# LabPowerSupply_CurrentModuleV1_0.net
KiCad netlist of a schematic drawn in EAGLE
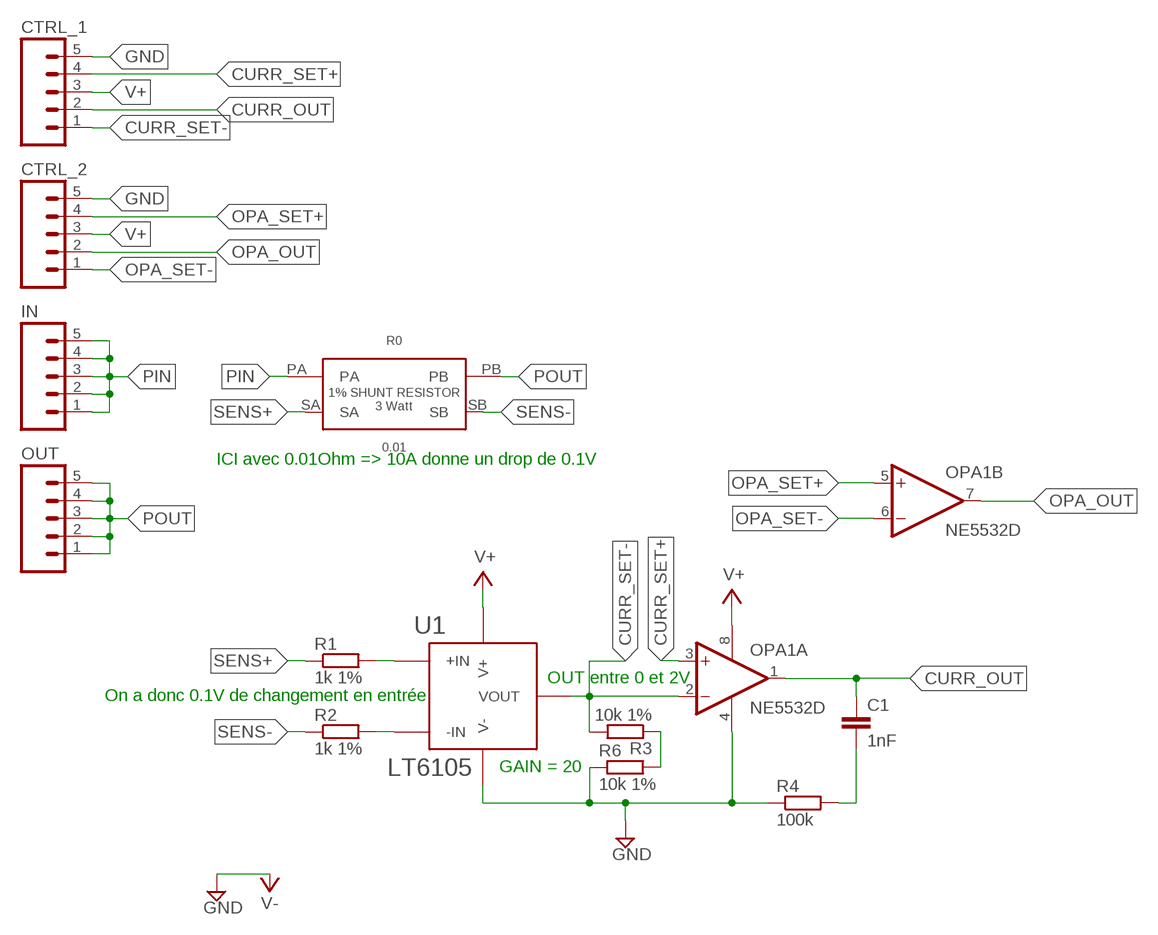
[diagram p0: schematic, sheet 1]

(export (version "E")
  (design (tool "Eeschema 10.0.6"))
  (components
    (comp (ref "C1")
      (value "1nF")
      (footprint "eagle-import:C1206K")
      (libsource (lib "eagle-import") (part "C-EUC1206K"))
    )
    (comp (ref "CTRL_1")
      (value "M05PTH_LONGPADS")
      (footprint "eagle-import:1X05_LONGPADS")
      (libsource (lib "eagle-import") (part "M05PTH_LONGPADS"))
    )
    (comp (ref "CTRL_2")
      (value "M05PTH_LONGPADS")
      (footprint "eagle-import:1X05_LONGPADS")
      (libsource (lib "eagle-import") (part "M05PTH_LONGPADS"))
    )
    (comp (ref "IN")
      (value "M05PTH_LONGPADS")
      (footprint "eagle-import:1X05_LONGPADS")
      (libsource (lib "eagle-import") (part "M05PTH_LONGPADS"))
    )
    (comp (ref "OPA1")
      (value "NE5532D")
      (footprint "eagle-import:SO08")
      (libsource (lib "eagle-import") (part "NE5532D"))
    )
    (comp (ref "OUT")
      (value "M05PTH_LONGPADS")
      (footprint "eagle-import:1X05_LONGPADS")
      (libsource (lib "eagle-import") (part "M05PTH_LONGPADS"))
    )
    (comp (ref "R0")
      (value "0.01")
      (footprint "eagle-import:3637R")
      (libsource (lib "eagle-import") (part "WSL3637R0100FEA"))
    )
    (comp (ref "R1")
      (value "1k 1%")
      (footprint "eagle-import:R1206")
      (libsource (lib "eagle-import") (part "R-EU_R1206"))
    )
    (comp (ref "R2")
      (value "1k 1%")
      (footprint "eagle-import:R1206")
      (libsource (lib "eagle-import") (part "R-EU_R1206"))
    )
    (comp (ref "R3")
      (value "10k 1%")
      (footprint "eagle-import:R1206")
      (libsource (lib "eagle-import") (part "R-EU_R1206"))
    )
    (comp (ref "R4")
      (value "100k")
      (footprint "eagle-import:R1206")
      (libsource (lib "eagle-import") (part "R-EU_R1206"))
    )
    (comp (ref "R6")
      (value "10k 1%")
      (footprint "eagle-import:R1206")
      (libsource (lib "eagle-import") (part "R-EU_R1206"))
    )
    (comp (ref "U1")
      (value "LT6105")
      (footprint "eagle-import:MSOP_8")
      (libsource (lib "eagle-import") (part "LT6105_MSOP_8"))
    )
  )
  (nets
    (net (code "1") (name "CURR_OUT") (class "Default")
      (node (ref "C1") (pin "1") (pinfunction "1_1") (pintype "passive"))
      (node (ref "CTRL_1") (pin "2") (pinfunction "2_2") (pintype "passive"))
      (node (ref "OPA1") (pin "1") (pinfunction "OUT_1") (pintype "output"))
    )
    (net (code "2") (name "CURR_SET+") (class "Default")
      (node (ref "CTRL_1") (pin "4") (pinfunction "4_4") (pintype "passive"))
      (node (ref "OPA1") (pin "3") (pinfunction "+IN_3") (pintype "input"))
    )
    (net (code "3") (name "CURR_SET-") (class "Default")
      (node (ref "CTRL_1") (pin "1") (pinfunction "1_1") (pintype "passive"))
      (node (ref "OPA1") (pin "2") (pinfunction "-IN_2") (pintype "input"))
      (node (ref "R3") (pin "2") (pinfunction "2_2") (pintype "passive"))
      (node (ref "U1") (pin "5") (pinfunction "VOUT_5") (pintype "output"))
    )
    (net (code "4") (name "GND") (class "Default")
      (node (ref "CTRL_1") (pin "5") (pinfunction "5_5") (pintype "passive"))
      (node (ref "CTRL_2") (pin "5") (pinfunction "5_5") (pintype "passive"))
      (node (ref "OPA1") (pin "4") (pinfunction "V-_4") (pintype "power_in"))
      (node (ref "R4") (pin "1") (pinfunction "1_1") (pintype "passive"))
      (node (ref "R6") (pin "1") (pinfunction "1_1") (pintype "passive"))
      (node (ref "U1") (pin "4") (pinfunction "V-_4") (pintype "power_in"))
    )
    (net (code "5") (name "Net-(C1-Pad2)") (class "Default")
      (node (ref "C1") (pin "2") (pinfunction "2_2") (pintype "passive"))
      (node (ref "R4") (pin "2") (pinfunction "2_2") (pintype "passive"))
    )
    (net (code "6") (name "Net-(R3-Pad1)") (class "Default")
      (node (ref "R3") (pin "1") (pinfunction "1_1") (pintype "passive"))
      (node (ref "R6") (pin "2") (pinfunction "2_2") (pintype "passive"))
    )
    (net (code "7") (name "Net-(U1-+IN)") (class "Default")
      (node (ref "R1") (pin "2") (pinfunction "2_2") (pintype "passive"))
      (node (ref "U1") (pin "8") (pinfunction "+IN_8") (pintype "input"))
    )
    (net (code "8") (name "Net-(U1--IN)") (class "Default")
      (node (ref "R2") (pin "2") (pinfunction "2_2") (pintype "passive"))
      (node (ref "U1") (pin "1") (pinfunction "-IN_1") (pintype "input"))
    )
    (net (code "9") (name "OPA_OUT") (class "Default")
      (node (ref "CTRL_2") (pin "2") (pinfunction "2_2") (pintype "passive"))
      (node (ref "OPA1") (pin "7") (pinfunction "OUT_7") (pintype "output"))
    )
    (net (code "10") (name "OPA_SET+") (class "Default")
      (node (ref "CTRL_2") (pin "4") (pinfunction "4_4") (pintype "passive"))
      (node (ref "OPA1") (pin "5") (pinfunction "+IN_5") (pintype "input"))
    )
    (net (code "11") (name "OPA_SET-") (class "Default")
      (node (ref "CTRL_2") (pin "1") (pinfunction "1_1") (pintype "passive"))
      (node (ref "OPA1") (pin "6") (pinfunction "-IN_6") (pintype "input"))
    )
    (net (code "12") (name "PIN") (class "Default")
      (node (ref "IN") (pin "1") (pinfunction "1_1") (pintype "passive"))
      (node (ref "IN") (pin "2") (pinfunction "2_2") (pintype "passive"))
      (node (ref "IN") (pin "3") (pinfunction "3_3") (pintype "passive"))
      (node (ref "IN") (pin "4") (pinfunction "4_4") (pintype "passive"))
      (node (ref "IN") (pin "5") (pinfunction "5_5") (pintype "passive"))
      (node (ref "R0") (pin "PA") (pinfunction "PA_PA") (pintype "bidirectional"))
    )
    (net (code "13") (name "POUT") (class "Default")
      (node (ref "OUT") (pin "1") (pinfunction "1_1") (pintype "passive"))
      (node (ref "OUT") (pin "2") (pinfunction "2_2") (pintype "passive"))
      (node (ref "OUT") (pin "3") (pinfunction "3_3") (pintype "passive"))
      (node (ref "OUT") (pin "4") (pinfunction "4_4") (pintype "passive"))
      (node (ref "OUT") (pin "5") (pinfunction "5_5") (pintype "passive"))
      (node (ref "R0") (pin "PB") (pinfunction "PB_PB") (pintype "bidirectional"))
    )
    (net (code "14") (name "SENS+") (class "Default")
      (node (ref "R0") (pin "SA") (pinfunction "SA_SA") (pintype "bidirectional"))
      (node (ref "R1") (pin "1") (pinfunction "1_1") (pintype "passive"))
    )
    (net (code "15") (name "SENS-") (class "Default")
      (node (ref "R0") (pin "SB") (pinfunction "SB_SB") (pintype "bidirectional"))
      (node (ref "R2") (pin "1") (pinfunction "1_1") (pintype "passive"))
    )
    (net (code "16") (name "V+") (class "Default")
      (node (ref "CTRL_1") (pin "3") (pinfunction "3_3") (pintype "passive"))
      (node (ref "CTRL_2") (pin "3") (pinfunction "3_3") (pintype "passive"))
      (node (ref "OPA1") (pin "8") (pinfunction "V+_8") (pintype "power_in"))
      (node (ref "U1") (pin "2") (pinfunction "V+_2") (pintype "power_in"))
    )
  )
)
